# audio.net
KiCad netlist of a schematic drawn in Altium Designer
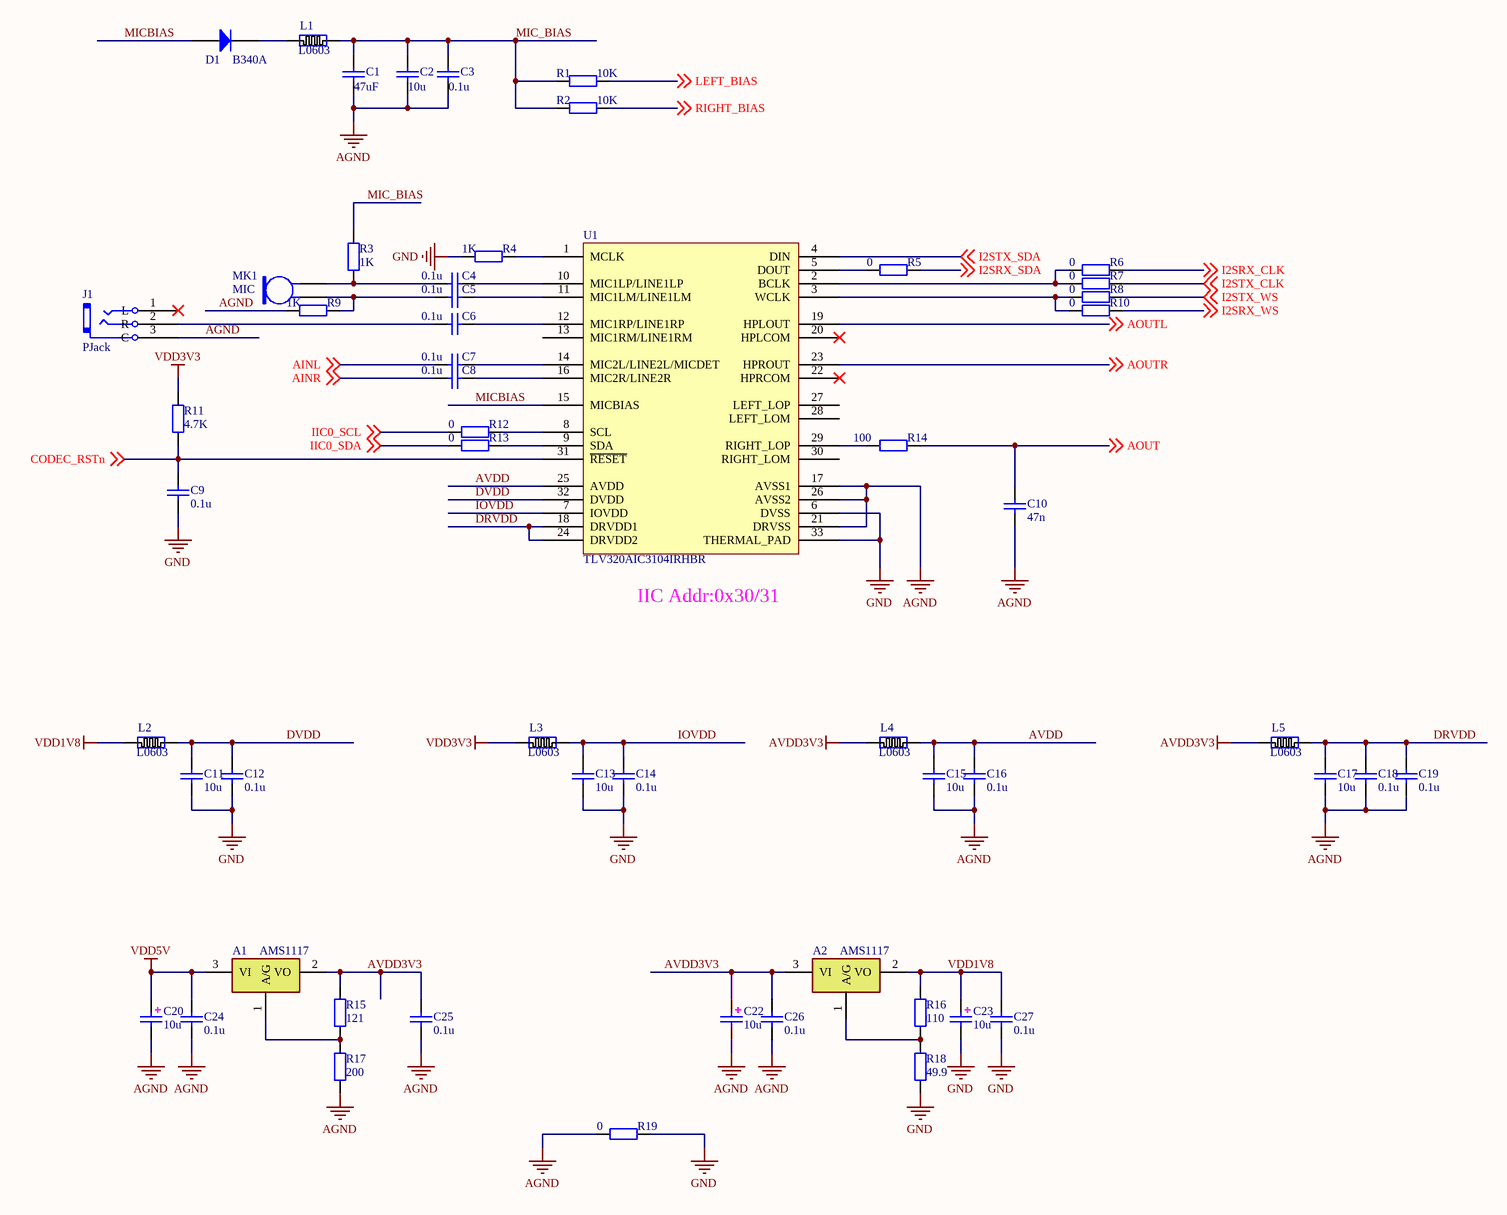
[diagram p0: audio.SchDoc]

(export (version "E")
  (design (tool "Eeschema 10.0.6"))
  (components
    (comp (ref "A1")
      (value "AMS1117")
      (footprint "ASM1117-A")
      (description "1117 LDO")
      (libsource (lib "lpc2368") (part "AMS1117"))
    )
    (comp (ref "A2")
      (value "AMS1117")
      (footprint "ASM1117-A")
      (description "1117 LDO")
      (libsource (lib "lpc2368") (part "AMS1117"))
    )
    (comp (ref "C1")
      (value "47uF")
      (footprint "C0805")
      (description "0603 Capacitor without Polarity")
      (libsource (lib "lpc2368") (part "CAP0603"))
    )
    (comp (ref "C2")
      (value "10u")
      (footprint "C0603")
      (description "0603 Capacitor without Polarity")
      (libsource (lib "lpc2368") (part "CAP0603"))
    )
    (comp (ref "C3")
      (value "0.1u")
      (footprint "C0603")
      (description "0603 Capacitor without Polarity")
      (libsource (lib "lpc2368") (part "CAP0603"))
    )
    (comp (ref "C4")
      (value "0.1u")
      (footprint "C0603")
      (description "0603 Capacitor without Polarity")
      (libsource (lib "lpc2368") (part "CAP0603"))
    )
    (comp (ref "C5")
      (value "0.1u")
      (footprint "C0603")
      (description "0603 Capacitor without Polarity")
      (libsource (lib "lpc2368") (part "CAP0603"))
    )
    (comp (ref "C6")
      (value "0.1u")
      (footprint "C0603")
      (description "0603 Capacitor without Polarity")
      (libsource (lib "lpc2368") (part "CAP0603"))
    )
    (comp (ref "C7")
      (value "0.1u")
      (footprint "C0603")
      (description "0603 Capacitor without Polarity")
      (libsource (lib "lpc2368") (part "CAP0603"))
    )
    (comp (ref "C8")
      (value "0.1u")
      (footprint "C0603")
      (description "0603 Capacitor without Polarity")
      (libsource (lib "lpc2368") (part "CAP0603"))
    )
    (comp (ref "C9")
      (value "0.1u")
      (footprint "C0603")
      (description "0603 Capacitor without Polarity")
      (libsource (lib "lpc2368") (part "CAP0603"))
    )
    (comp (ref "C10")
      (value "47n")
      (footprint "C0603")
      (description "0603 Capacitor without Polarity")
      (libsource (lib "lpc2368") (part "CAP0603"))
    )
    (comp (ref "C11")
      (value "10u")
      (footprint "C0603")
      (description "0603 Capacitor without Polarity")
      (libsource (lib "lpc2368") (part "CAP0603"))
    )
    (comp (ref "C12")
      (value "0.1u")
      (footprint "C0603")
      (description "0603 Capacitor without Polarity")
      (libsource (lib "lpc2368") (part "CAP0603"))
    )
    (comp (ref "C13")
      (value "10u")
      (footprint "C0603")
      (description "0603 Capacitor without Polarity")
      (libsource (lib "lpc2368") (part "CAP0603"))
    )
    (comp (ref "C14")
      (value "0.1u")
      (footprint "C0603")
      (description "0603 Capacitor without Polarity")
      (libsource (lib "lpc2368") (part "CAP0603"))
    )
    (comp (ref "C15")
      (value "10u")
      (footprint "C0603")
      (description "0603 Capacitor without Polarity")
      (libsource (lib "lpc2368") (part "CAP0603"))
    )
    (comp (ref "C16")
      (value "0.1u")
      (footprint "C0603")
      (description "0603 Capacitor without Polarity")
      (libsource (lib "lpc2368") (part "CAP0603"))
    )
    (comp (ref "C17")
      (value "10u")
      (footprint "C0603")
      (description "0603 Capacitor without Polarity")
      (libsource (lib "lpc2368") (part "CAP0603"))
    )
    (comp (ref "C18")
      (value "0.1u")
      (footprint "C0603")
      (description "0603 Capacitor without Polarity")
      (libsource (lib "lpc2368") (part "CAP0603"))
    )
    (comp (ref "C19")
      (value "0.1u")
      (footprint "C0603")
      (description "0603 Capacitor without Polarity")
      (libsource (lib "lpc2368") (part "CAP0603"))
    )
    (comp (ref "C20")
      (value "10u")
      (footprint "C1210")
      (description "钽电容1210封装")
      (libsource (lib "lpc2368") (part "DCAP"))
    )
    (comp (ref "C22")
      (value "10u")
      (footprint "C1210")
      (description "钽电容1210封装")
      (libsource (lib "lpc2368") (part "DCAP"))
    )
    (comp (ref "C23")
      (value "10u")
      (footprint "C1210")
      (description "钽电容1210封装")
      (libsource (lib "lpc2368") (part "DCAP"))
    )
    (comp (ref "C24")
      (value "0.1u")
      (footprint "C0603")
      (description "0603 Capacitor without Polarity")
      (libsource (lib "lpc2368") (part "CAP0603"))
    )
    (comp (ref "C25")
      (value "0.1u")
      (footprint "C0603")
      (description "0603 Capacitor without Polarity")
      (libsource (lib "lpc2368") (part "CAP0603"))
    )
    (comp (ref "C26")
      (value "0.1u")
      (footprint "C0603")
      (description "0603 Capacitor without Polarity")
      (libsource (lib "lpc2368") (part "CAP0603"))
    )
    (comp (ref "C27")
      (value "0.1u")
      (footprint "C0603")
      (description "0603 Capacitor without Polarity")
      (libsource (lib "lpc2368") (part "CAP0603"))
    )
    (comp (ref "D1") (value "B340A") (footprint "D2112") (libsource (lib "lpc2368") (part "B340A")))
    (comp (ref "J1")
      (value "PJack")
      (footprint "ADIO")
      (description "3.5mm EPhone Jack")
      (libsource (lib "lpc2368") (part "PJack"))
    )
    (comp (ref "L1")
      (value "L0603")
      (footprint "L0603")
      (description "0603 Inductor")
      (libsource (lib "lpc2368") (part "L0603"))
    )
    (comp (ref "L2")
      (value "L0603")
      (footprint "L0603")
      (description "0603 Inductor")
      (libsource (lib "lpc2368") (part "L0603"))
    )
    (comp (ref "L3")
      (value "L0603")
      (footprint "L0603")
      (description "0603 Inductor")
      (libsource (lib "lpc2368") (part "L0603"))
    )
    (comp (ref "L4")
      (value "L0603")
      (footprint "L0603")
      (description "0603 Inductor")
      (libsource (lib "lpc2368") (part "L0603"))
    )
    (comp (ref "L5")
      (value "L0603")
      (footprint "L0603")
      (description "0603 Inductor")
      (libsource (lib "lpc2368") (part "L0603"))
    )
    (comp (ref "MK1")
      (value "MIC")
      (footprint "MIC")
      (description "Microphone")
      (libsource (lib "lpc2368") (part "MICROPHONE"))
    )
    (comp (ref "R1")
      (value "10K")
      (footprint "R0603")
      (description "0603 Resistor")
      (libsource (lib "") (part "RES0603_1"))
    )
    (comp (ref "R2")
      (value "10K")
      (footprint "R0603")
      (description "0603 Resistor")
      (libsource (lib "") (part "RES0603_1"))
    )
    (comp (ref "R3")
      (value "1K")
      (footprint "R0603")
      (description "0603 Resistor")
      (libsource (lib "") (part "RES0603_2"))
    )
    (comp (ref "R4")
      (value "1K")
      (footprint "R0603")
      (description "0603 Resistor")
      (libsource (lib "lpc2368") (part "RES0603"))
    )
    (comp (ref "R5")
      (value "0")
      (footprint "R0603")
      (description "0603 Resistor")
      (libsource (lib "lpc2368") (part "RES0603"))
    )
    (comp (ref "R6")
      (value "0")
      (footprint "R0603")
      (description "0603 Resistor")
      (libsource (lib "lpc2368") (part "RES0603"))
    )
    (comp (ref "R7")
      (value "0")
      (footprint "R0603")
      (description "0603 Resistor")
      (libsource (lib "lpc2368") (part "RES0603"))
    )
    (comp (ref "R8")
      (value "0")
      (footprint "R0603")
      (description "0603 Resistor")
      (libsource (lib "lpc2368") (part "RES0603"))
    )
    (comp (ref "R9")
      (value "1K")
      (footprint "R0603")
      (description "0603 Resistor")
      (libsource (lib "") (part "RES0603_1"))
    )
    (comp (ref "R10")
      (value "0")
      (footprint "R0603")
      (description "0603 Resistor")
      (libsource (lib "lpc2368") (part "RES0603"))
    )
    (comp (ref "R11")
      (value "4.7K")
      (footprint "R0603")
      (description "0603 Resistor")
      (libsource (lib "") (part "RES0603_3"))
    )
    (comp (ref "R12")
      (value "0")
      (footprint "R0603")
      (description "0603 Resistor")
      (libsource (lib "lpc2368") (part "RES0603"))
    )
    (comp (ref "R13")
      (value "0")
      (footprint "R0603")
      (description "0603 Resistor")
      (libsource (lib "lpc2368") (part "RES0603"))
    )
    (comp (ref "R14")
      (value "100")
      (footprint "R0603")
      (description "0603 Resistor")
      (libsource (lib "lpc2368") (part "RES0603"))
    )
    (comp (ref "R15")
      (value "121")
      (footprint "R0603")
      (description "0603 Resistor")
      (libsource (lib "") (part "RES0603_2"))
    )
    (comp (ref "R16")
      (value "110")
      (footprint "R0603")
      (description "0603 Resistor")
      (libsource (lib "") (part "RES0603_2"))
    )
    (comp (ref "R17")
      (value "200")
      (footprint "R0603")
      (description "0603 Resistor")
      (libsource (lib "") (part "RES0603_2"))
    )
    (comp (ref "R18")
      (value "49.9")
      (footprint "R0603")
      (description "0603 Resistor")
      (libsource (lib "") (part "RES0603_2"))
    )
    (comp (ref "R19")
      (value "0")
      (footprint "R0603")
      (description "0603 Resistor")
      (libsource (lib "lpc2368") (part "RES0603"))
    )
    (comp (ref "U1")
      (value "TLV320AIC3104IRHBR")
      (footprint "QFN33-I20-200200")
      (description "TI AUDIO CODEC")
      (libsource (lib "lpc2368") (part "TLV320AIC3104IRHBR"))
    )
  )
  (nets
    (net (code "1") (name "/AVDD") (class "Default")
      (node (ref "C15") (pin "2") (pinfunction "2_2") (pintype "passive"))
      (node (ref "C16") (pin "2") (pinfunction "2_2") (pintype "passive"))
      (node (ref "L4") (pin "2") (pinfunction "2_2") (pintype "passive"))
      (node (ref "U1") (pin "25") (pinfunction "AVDD_25") (pintype "passive"))
    )
    (net (code "2") (name "/DRVDD") (class "Default")
      (node (ref "C17") (pin "2") (pinfunction "2_2") (pintype "passive"))
      (node (ref "C18") (pin "2") (pinfunction "2_2") (pintype "passive"))
      (node (ref "C19") (pin "2") (pinfunction "2_2") (pintype "passive"))
      (node (ref "L5") (pin "2") (pinfunction "2_2") (pintype "passive"))
      (node (ref "U1") (pin "18") (pinfunction "DRVDD1_18") (pintype "passive"))
      (node (ref "U1") (pin "24") (pinfunction "DRVDD2_24") (pintype "passive"))
    )
    (net (code "3") (name "/DVDD") (class "Default")
      (node (ref "C11") (pin "2") (pinfunction "2_2") (pintype "passive"))
      (node (ref "C12") (pin "2") (pinfunction "2_2") (pintype "passive"))
      (node (ref "L2") (pin "2") (pinfunction "2_2") (pintype "passive"))
      (node (ref "U1") (pin "32") (pinfunction "DVDD_32") (pintype "passive"))
    )
    (net (code "4") (name "/IOVDD") (class "Default")
      (node (ref "C13") (pin "2") (pinfunction "2_2") (pintype "passive"))
      (node (ref "C14") (pin "2") (pinfunction "2_2") (pintype "passive"))
      (node (ref "L3") (pin "2") (pinfunction "2_2") (pintype "passive"))
      (node (ref "U1") (pin "7") (pinfunction "IOVDD_7") (pintype "passive"))
    )
    (net (code "5") (name "/MICBIAS") (class "Default")
      (node (ref "D1") (pin "A") (pinfunction "A_A") (pintype "passive"))
      (node (ref "U1") (pin "15") (pinfunction "MICBIAS_15") (pintype "passive"))
    )
    (net (code "6") (name "/MIC_BIAS") (class "Default")
      (node (ref "C1") (pin "2") (pinfunction "2_2") (pintype "passive"))
      (node (ref "C2") (pin "2") (pinfunction "2_2") (pintype "passive"))
      (node (ref "C3") (pin "2") (pinfunction "2_2") (pintype "passive"))
      (node (ref "L1") (pin "2") (pinfunction "2_2") (pintype "passive"))
      (node (ref "R1") (pin "2") (pinfunction "2_2") (pintype "passive"))
      (node (ref "R2") (pin "2") (pinfunction "2_2") (pintype "passive"))
      (node (ref "R3") (pin "2") (pinfunction "2_2") (pintype "passive"))
    )
    (net (code "7") (name "AGND") (class "Default")
      (node (ref "C1") (pin "1") (pinfunction "1_1") (pintype "passive"))
      (node (ref "C10") (pin "1") (pinfunction "1_1") (pintype "passive"))
      (node (ref "C15") (pin "1") (pinfunction "1_1") (pintype "passive"))
      (node (ref "C16") (pin "1") (pinfunction "1_1") (pintype "passive"))
      (node (ref "C17") (pin "1") (pinfunction "1_1") (pintype "passive"))
      (node (ref "C18") (pin "1") (pinfunction "1_1") (pintype "passive"))
      (node (ref "C19") (pin "1") (pinfunction "1_1") (pintype "passive"))
      (node (ref "C2") (pin "1") (pinfunction "1_1") (pintype "passive"))
      (node (ref "C20") (pin "2") (pinfunction "2_2") (pintype "passive"))
      (node (ref "C22") (pin "2") (pinfunction "2_2") (pintype "passive"))
      (node (ref "C24") (pin "1") (pinfunction "1_1") (pintype "passive"))
      (node (ref "C25") (pin "1") (pinfunction "1_1") (pintype "passive"))
      (node (ref "C26") (pin "1") (pinfunction "1_1") (pintype "passive"))
      (node (ref "C3") (pin "1") (pinfunction "1_1") (pintype "passive"))
      (node (ref "J1") (pin "3") (pinfunction "C_3") (pintype "passive"))
      (node (ref "R17") (pin "1") (pinfunction "1_1") (pintype "passive"))
      (node (ref "R19") (pin "1") (pinfunction "1_1") (pintype "passive"))
      (node (ref "R9") (pin "2") (pinfunction "2_2") (pintype "passive"))
      (node (ref "U1") (pin "17") (pinfunction "AVSS1_17") (pintype "passive"))
      (node (ref "U1") (pin "21") (pinfunction "DRVSS_21") (pintype "passive"))
      (node (ref "U1") (pin "26") (pinfunction "AVSS2_26") (pintype "passive"))
    )
    (net (code "8") (name "AINL") (class "Default")
      (node (ref "C7") (pin "2") (pinfunction "2_2") (pintype "passive"))
    )
    (net (code "9") (name "AINR") (class "Default")
      (node (ref "C8") (pin "2") (pinfunction "2_2") (pintype "passive"))
    )
    (net (code "10") (name "AOUT") (class "Default")
      (node (ref "C10") (pin "2") (pinfunction "2_2") (pintype "passive"))
      (node (ref "R14") (pin "2") (pinfunction "2_2") (pintype "passive"))
    )
    (net (code "11") (name "AOUTL") (class "Default")
      (node (ref "U1") (pin "19") (pinfunction "HPLOUT_19") (pintype "passive"))
    )
    (net (code "12") (name "AOUTR") (class "Default")
      (node (ref "U1") (pin "23") (pinfunction "HPROUT_23") (pintype "passive"))
    )
    (net (code "13") (name "AVDD3V3") (class "Default")
      (node (ref "A1") (pin "2") (pinfunction "VO_2") (pintype "passive"))
      (node (ref "A2") (pin "3") (pinfunction "VI_3") (pintype "passive"))
      (node (ref "C22") (pin "1") (pinfunction "1_1") (pintype "passive"))
      (node (ref "C25") (pin "2") (pinfunction "2_2") (pintype "passive"))
      (node (ref "C26") (pin "2") (pinfunction "2_2") (pintype "passive"))
      (node (ref "L4") (pin "1") (pinfunction "1_1") (pintype "passive"))
      (node (ref "L5") (pin "1") (pinfunction "1_1") (pintype "passive"))
      (node (ref "R15") (pin "2") (pinfunction "2_2") (pintype "passive"))
    )
    (net (code "14") (name "CODEC_RSTn") (class "Default")
      (node (ref "C9") (pin "2") (pinfunction "2_2") (pintype "passive"))
      (node (ref "R11") (pin "2") (pinfunction "2_2") (pintype "passive"))
      (node (ref "U1") (pin "31") (pinfunction "~{RESET}_31") (pintype "passive"))
    )
    (net (code "15") (name "GND") (class "Default")
      (node (ref "C11") (pin "1") (pinfunction "1_1") (pintype "passive"))
      (node (ref "C12") (pin "1") (pinfunction "1_1") (pintype "passive"))
      (node (ref "C13") (pin "1") (pinfunction "1_1") (pintype "passive"))
      (node (ref "C14") (pin "1") (pinfunction "1_1") (pintype "passive"))
      (node (ref "C23") (pin "2") (pinfunction "2_2") (pintype "passive"))
      (node (ref "C27") (pin "1") (pinfunction "1_1") (pintype "passive"))
      (node (ref "C9") (pin "1") (pinfunction "1_1") (pintype "passive"))
      (node (ref "R18") (pin "1") (pinfunction "1_1") (pintype "passive"))
      (node (ref "R19") (pin "2") (pinfunction "2_2") (pintype "passive"))
      (node (ref "R4") (pin "1") (pinfunction "1_1") (pintype "passive"))
      (node (ref "U1") (pin "33") (pinfunction "THERMAL_PAD_33") (pintype "passive"))
      (node (ref "U1") (pin "6") (pinfunction "DVSS_6") (pintype "passive"))
    )
    (net (code "16") (name "I2SRX_CLK") (class "Default")
      (node (ref "R6") (pin "2") (pinfunction "2_2") (pintype "passive"))
    )
    (net (code "17") (name "I2SRX_SDA") (class "Default")
      (node (ref "R5") (pin "2") (pinfunction "2_2") (pintype "passive"))
    )
    (net (code "18") (name "I2SRX_WS") (class "Default")
      (node (ref "R10") (pin "2") (pinfunction "2_2") (pintype "passive"))
    )
    (net (code "19") (name "I2STX_CLK") (class "Default")
      (node (ref "R7") (pin "2") (pinfunction "2_2") (pintype "passive"))
    )
    (net (code "20") (name "I2STX_SDA") (class "Default")
      (node (ref "U1") (pin "4") (pinfunction "DIN_4") (pintype "passive"))
    )
    (net (code "21") (name "I2STX_WS") (class "Default")
      (node (ref "R8") (pin "2") (pinfunction "2_2") (pintype "passive"))
    )
    (net (code "22") (name "IIC0_SCL") (class "Default")
      (node (ref "R12") (pin "1") (pinfunction "1_1") (pintype "passive"))
    )
    (net (code "23") (name "IIC0_SDA") (class "Default")
      (node (ref "R13") (pin "1") (pinfunction "1_1") (pintype "passive"))
    )
    (net (code "24") (name "LEFT_BIAS") (class "Default")
      (node (ref "R1") (pin "1") (pinfunction "1_1") (pintype "passive"))
    )
    (net (code "25") (name "Net-(A1-A{slash}G)") (class "Default")
      (node (ref "A1") (pin "1") (pinfunction "A/G_1") (pintype "passive"))
      (node (ref "R15") (pin "1") (pinfunction "1_1") (pintype "passive"))
      (node (ref "R17") (pin "2") (pinfunction "2_2") (pintype "passive"))
    )
    (net (code "26") (name "Net-(A2-A{slash}G)") (class "Default")
      (node (ref "A2") (pin "1") (pinfunction "A/G_1") (pintype "passive"))
      (node (ref "R16") (pin "1") (pinfunction "1_1") (pintype "passive"))
      (node (ref "R18") (pin "2") (pinfunction "2_2") (pintype "passive"))
    )
    (net (code "27") (name "Net-(C4-Pad2)") (class "Default")
      (node (ref "C4") (pin "2") (pinfunction "2_2") (pintype "passive"))
      (node (ref "MK1") (pin "2") (pinfunction "2_2") (pintype "passive"))
      (node (ref "R3") (pin "1") (pinfunction "1_1") (pintype "passive"))
    )
    (net (code "28") (name "Net-(C5-Pad2)") (class "Default")
      (node (ref "C5") (pin "2") (pinfunction "2_2") (pintype "passive"))
      (node (ref "MK1") (pin "1") (pinfunction "1_1") (pintype "passive"))
      (node (ref "R9") (pin "1") (pinfunction "1_1") (pintype "passive"))
    )
    (net (code "29") (name "Net-(D1-PadK)") (class "Default")
      (node (ref "D1") (pin "K") (pinfunction "K_K") (pintype "passive"))
      (node (ref "L1") (pin "1") (pinfunction "1_1") (pintype "passive"))
    )
    (net (code "30") (name "Net-(J1-R)") (class "Default")
      (node (ref "C6") (pin "2") (pinfunction "2_2") (pintype "passive"))
      (node (ref "J1") (pin "2") (pinfunction "R_2") (pintype "passive"))
    )
    (net (code "31") (name "Net-(U1-BCLK)") (class "Default")
      (node (ref "R6") (pin "1") (pinfunction "1_1") (pintype "passive"))
      (node (ref "R7") (pin "1") (pinfunction "1_1") (pintype "passive"))
      (node (ref "U1") (pin "2") (pinfunction "BCLK_2") (pintype "passive"))
    )
    (net (code "32") (name "Net-(U1-DOUT)") (class "Default")
      (node (ref "R5") (pin "1") (pinfunction "1_1") (pintype "passive"))
      (node (ref "U1") (pin "5") (pinfunction "DOUT_5") (pintype "passive"))
    )
    (net (code "33") (name "Net-(U1-MCLK)") (class "Default")
      (node (ref "R4") (pin "2") (pinfunction "2_2") (pintype "passive"))
      (node (ref "U1") (pin "1") (pinfunction "MCLK_1") (pintype "passive"))
    )
    (net (code "34") (name "Net-(U1-MIC1LM{slash}LINE1LM)") (class "Default")
      (node (ref "C5") (pin "1") (pinfunction "1_1") (pintype "passive"))
      (node (ref "U1") (pin "11") (pinfunction "MIC1LM/LINE1LM_11") (pintype "passive"))
    )
    (net (code "35") (name "Net-(U1-MIC1LP{slash}LINE1LP)") (class "Default")
      (node (ref "C4") (pin "1") (pinfunction "1_1") (pintype "passive"))
      (node (ref "U1") (pin "10") (pinfunction "MIC1LP/LINE1LP_10") (pintype "passive"))
    )
    (net (code "36") (name "Net-(U1-MIC1RP{slash}LINE1RP)") (class "Default")
      (node (ref "C6") (pin "1") (pinfunction "1_1") (pintype "passive"))
      (node (ref "U1") (pin "12") (pinfunction "MIC1RP/LINE1RP_12") (pintype "passive"))
    )
    (net (code "37") (name "Net-(U1-MIC2L{slash}LINE2L{slash}MICDET)") (class "Default")
      (node (ref "C7") (pin "1") (pinfunction "1_1") (pintype "passive"))
      (node (ref "U1") (pin "14") (pinfunction "MIC2L/LINE2L/MICDET_14") (pintype "passive"))
    )
    (net (code "38") (name "Net-(U1-MIC2R{slash}LINE2R)") (class "Default")
      (node (ref "C8") (pin "1") (pinfunction "1_1") (pintype "passive"))
      (node (ref "U1") (pin "16") (pinfunction "MIC2R/LINE2R_16") (pintype "passive"))
    )
    (net (code "39") (name "Net-(U1-RIGHT_LOP)") (class "Default")
      (node (ref "R14") (pin "1") (pinfunction "1_1") (pintype "passive"))
      (node (ref "U1") (pin "29") (pinfunction "RIGHT_LOP_29") (pintype "passive"))
    )
    (net (code "40") (name "Net-(U1-SCL)") (class "Default")
      (node (ref "R12") (pin "2") (pinfunction "2_2") (pintype "passive"))
      (node (ref "U1") (pin "8") (pinfunction "SCL_8") (pintype "passive"))
    )
    (net (code "41") (name "Net-(U1-SDA)") (class "Default")
      (node (ref "R13") (pin "2") (pinfunction "2_2") (pintype "passive"))
      (node (ref "U1") (pin "9") (pinfunction "SDA_9") (pintype "passive"))
    )
    (net (code "42") (name "Net-(U1-WCLK)") (class "Default")
      (node (ref "R10") (pin "1") (pinfunction "1_1") (pintype "passive"))
      (node (ref "R8") (pin "1") (pinfunction "1_1") (pintype "passive"))
      (node (ref "U1") (pin "3") (pinfunction "WCLK_3") (pintype "passive"))
    )
    (net (code "43") (name "RIGHT_BIAS") (class "Default")
      (node (ref "R2") (pin "1") (pinfunction "1_1") (pintype "passive"))
    )
    (net (code "44") (name "VDD1V8") (class "Default")
      (node (ref "A2") (pin "2") (pinfunction "VO_2") (pintype "passive"))
      (node (ref "C23") (pin "1") (pinfunction "1_1") (pintype "passive"))
      (node (ref "C27") (pin "2") (pinfunction "2_2") (pintype "passive"))
      (node (ref "L2") (pin "1") (pinfunction "1_1") (pintype "passive"))
      (node (ref "R16") (pin "2") (pinfunction "2_2") (pintype "passive"))
    )
    (net (code "45") (name "VDD3V3") (class "Default")
      (node (ref "L3") (pin "1") (pinfunction "1_1") (pintype "passive"))
      (node (ref "R11") (pin "1") (pinfunction "1_1") (pintype "passive"))
    )
    (net (code "46") (name "VDD5V") (class "Default")
      (node (ref "A1") (pin "3") (pinfunction "VI_3") (pintype "passive"))
      (node (ref "C20") (pin "1") (pinfunction "1_1") (pintype "passive"))
      (node (ref "C24") (pin "2") (pinfunction "2_2") (pintype "passive"))
    )
    (net (code "47") (name "unconnected-(J1-L-Pad1)") (class "Default")
      (node (ref "J1") (pin "1") (pinfunction "L_1") (pintype "passive+no_connect"))
    )
    (net (code "48") (name "unconnected-(U1-HPLCOM-Pad20)") (class "Default")
      (node (ref "U1") (pin "20") (pinfunction "HPLCOM_20") (pintype "passive+no_connect"))
    )
    (net (code "49") (name "unconnected-(U1-HPRCOM-Pad22)") (class "Default")
      (node (ref "U1") (pin "22") (pinfunction "HPRCOM_22") (pintype "passive+no_connect"))
    )
    (net (code "50") (name "unconnected-(U1-LEFT_LOM-Pad28)") (class "Default")
      (node (ref "U1") (pin "28") (pinfunction "LEFT_LOM_28") (pintype "passive"))
    )
    (net (code "51") (name "unconnected-(U1-LEFT_LOP-Pad27)") (class "Default")
      (node (ref "U1") (pin "27") (pinfunction "LEFT_LOP_27") (pintype "passive"))
    )
    (net (code "52") (name "unconnected-(U1-MIC1RM{slash}LINE1RM-Pad13)") (class "Default")
      (node (ref "U1") (pin "13") (pinfunction "MIC1RM/LINE1RM_13") (pintype "passive"))
    )
    (net (code "53") (name "unconnected-(U1-RIGHT_LOM-Pad30)") (class "Default")
      (node (ref "U1") (pin "30") (pinfunction "RIGHT_LOM_30") (pintype "passive"))
    )
  )
)
